# gpio_adapter.net
KiCad netlist of a schematic drawn in EAGLE
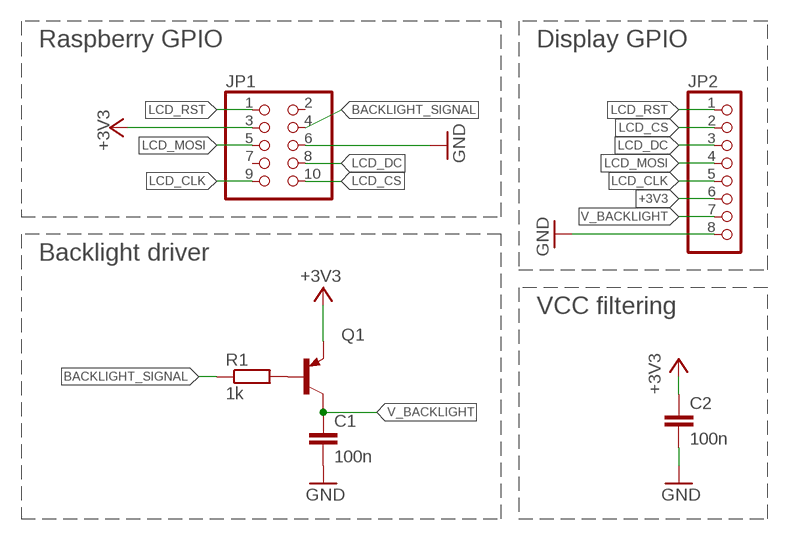
[diagram p0: schematic, sheet 1]

(export (version "E")
  (design (tool "Eeschema 10.0.6"))
  (components
    (comp (ref "C1")
      (value "100n")
      (footprint "eagle-import:C0805")
      (libsource (lib "eagle-import") (part "C-EUC0805"))
    )
    (comp (ref "C2")
      (value "100n")
      (footprint "eagle-import:C0805")
      (libsource (lib "eagle-import") (part "C-EUC0805"))
    )
    (comp (ref "JP1")
      (value "PINHD-2X5")
      (footprint "eagle-import:2X05")
      (libsource (lib "eagle-import") (part "PINHD-2X5"))
    )
    (comp (ref "JP2")
      (value "PINHD-1X8/90")
      (footprint "eagle-import:1X08_90")
      (libsource (lib "eagle-import") (part "PINHD-1X8/90"))
    )
    (comp (ref "Q1")
      (value "BC807-40SMD")
      (footprint "eagle-import:SOT23-BEC")
      (libsource (lib "eagle-import") (part "BC807SMD-40"))
    )
    (comp (ref "R1")
      (value "1k")
      (footprint "eagle-import:R0805")
      (libsource (lib "eagle-import") (part "R-EU_R0805"))
    )
  )
  (nets
    (net (code "1") (name "+3V3") (class "Default")
      (node (ref "C2") (pin "1") (pinfunction "1_1") (pintype "passive"))
      (node (ref "JP1") (pin "3") (pinfunction "3_3") (pintype "passive"))
      (node (ref "JP2") (pin "6") (pinfunction "6_6") (pintype "passive"))
      (node (ref "Q1") (pin "E") (pinfunction "E_E") (pintype "passive"))
    )
    (net (code "2") (name "BACKLIGHT_SIGNAL") (class "Default")
      (node (ref "JP1") (pin "4") (pinfunction "4_4") (pintype "passive"))
      (node (ref "R1") (pin "1") (pinfunction "1_1") (pintype "passive"))
    )
    (net (code "3") (name "GND") (class "Default")
      (node (ref "C1") (pin "2") (pinfunction "2_2") (pintype "passive"))
      (node (ref "C2") (pin "2") (pinfunction "2_2") (pintype "passive"))
      (node (ref "JP1") (pin "6") (pinfunction "6_6") (pintype "passive"))
      (node (ref "JP2") (pin "8") (pinfunction "8_8") (pintype "passive"))
    )
    (net (code "4") (name "LCD_CLK") (class "Default")
      (node (ref "JP1") (pin "9") (pinfunction "9_9") (pintype "passive"))
      (node (ref "JP2") (pin "5") (pinfunction "5_5") (pintype "passive"))
    )
    (net (code "5") (name "LCD_CS") (class "Default")
      (node (ref "JP1") (pin "10") (pinfunction "10_10") (pintype "passive"))
      (node (ref "JP2") (pin "2") (pinfunction "2_2") (pintype "passive"))
    )
    (net (code "6") (name "LCD_DC") (class "Default")
      (node (ref "JP1") (pin "8") (pinfunction "8_8") (pintype "passive"))
      (node (ref "JP2") (pin "3") (pinfunction "3_3") (pintype "passive"))
    )
    (net (code "7") (name "LCD_MOSI") (class "Default")
      (node (ref "JP1") (pin "5") (pinfunction "5_5") (pintype "passive"))
      (node (ref "JP2") (pin "4") (pinfunction "4_4") (pintype "passive"))
    )
    (net (code "8") (name "LCD_RST") (class "Default")
      (node (ref "JP1") (pin "1") (pinfunction "1_1") (pintype "passive"))
      (node (ref "JP2") (pin "1") (pinfunction "1_1") (pintype "passive"))
    )
    (net (code "9") (name "Net-(Q1-PadB)") (class "Default")
      (node (ref "Q1") (pin "B") (pinfunction "B_B") (pintype "passive"))
      (node (ref "R1") (pin "2") (pinfunction "2_2") (pintype "passive"))
    )
    (net (code "10") (name "V_BACKLIGHT") (class "Default")
      (node (ref "C1") (pin "1") (pinfunction "1_1") (pintype "passive"))
      (node (ref "JP2") (pin "7") (pinfunction "7_7") (pintype "passive"))
      (node (ref "Q1") (pin "C") (pinfunction "C_C") (pintype "passive"))
    )
    (net (code "11") (name "unconnected-(JP1-Pad2)") (class "Default")
      (node (ref "JP1") (pin "2") (pinfunction "2_2") (pintype "passive"))
    )
    (net (code "12") (name "unconnected-(JP1-Pad7)") (class "Default")
      (node (ref "JP1") (pin "7") (pinfunction "7_7") (pintype "passive"))
    )
  )
)
